# B156X.net
KiCad netlist of a schematic drawn in EAGLE
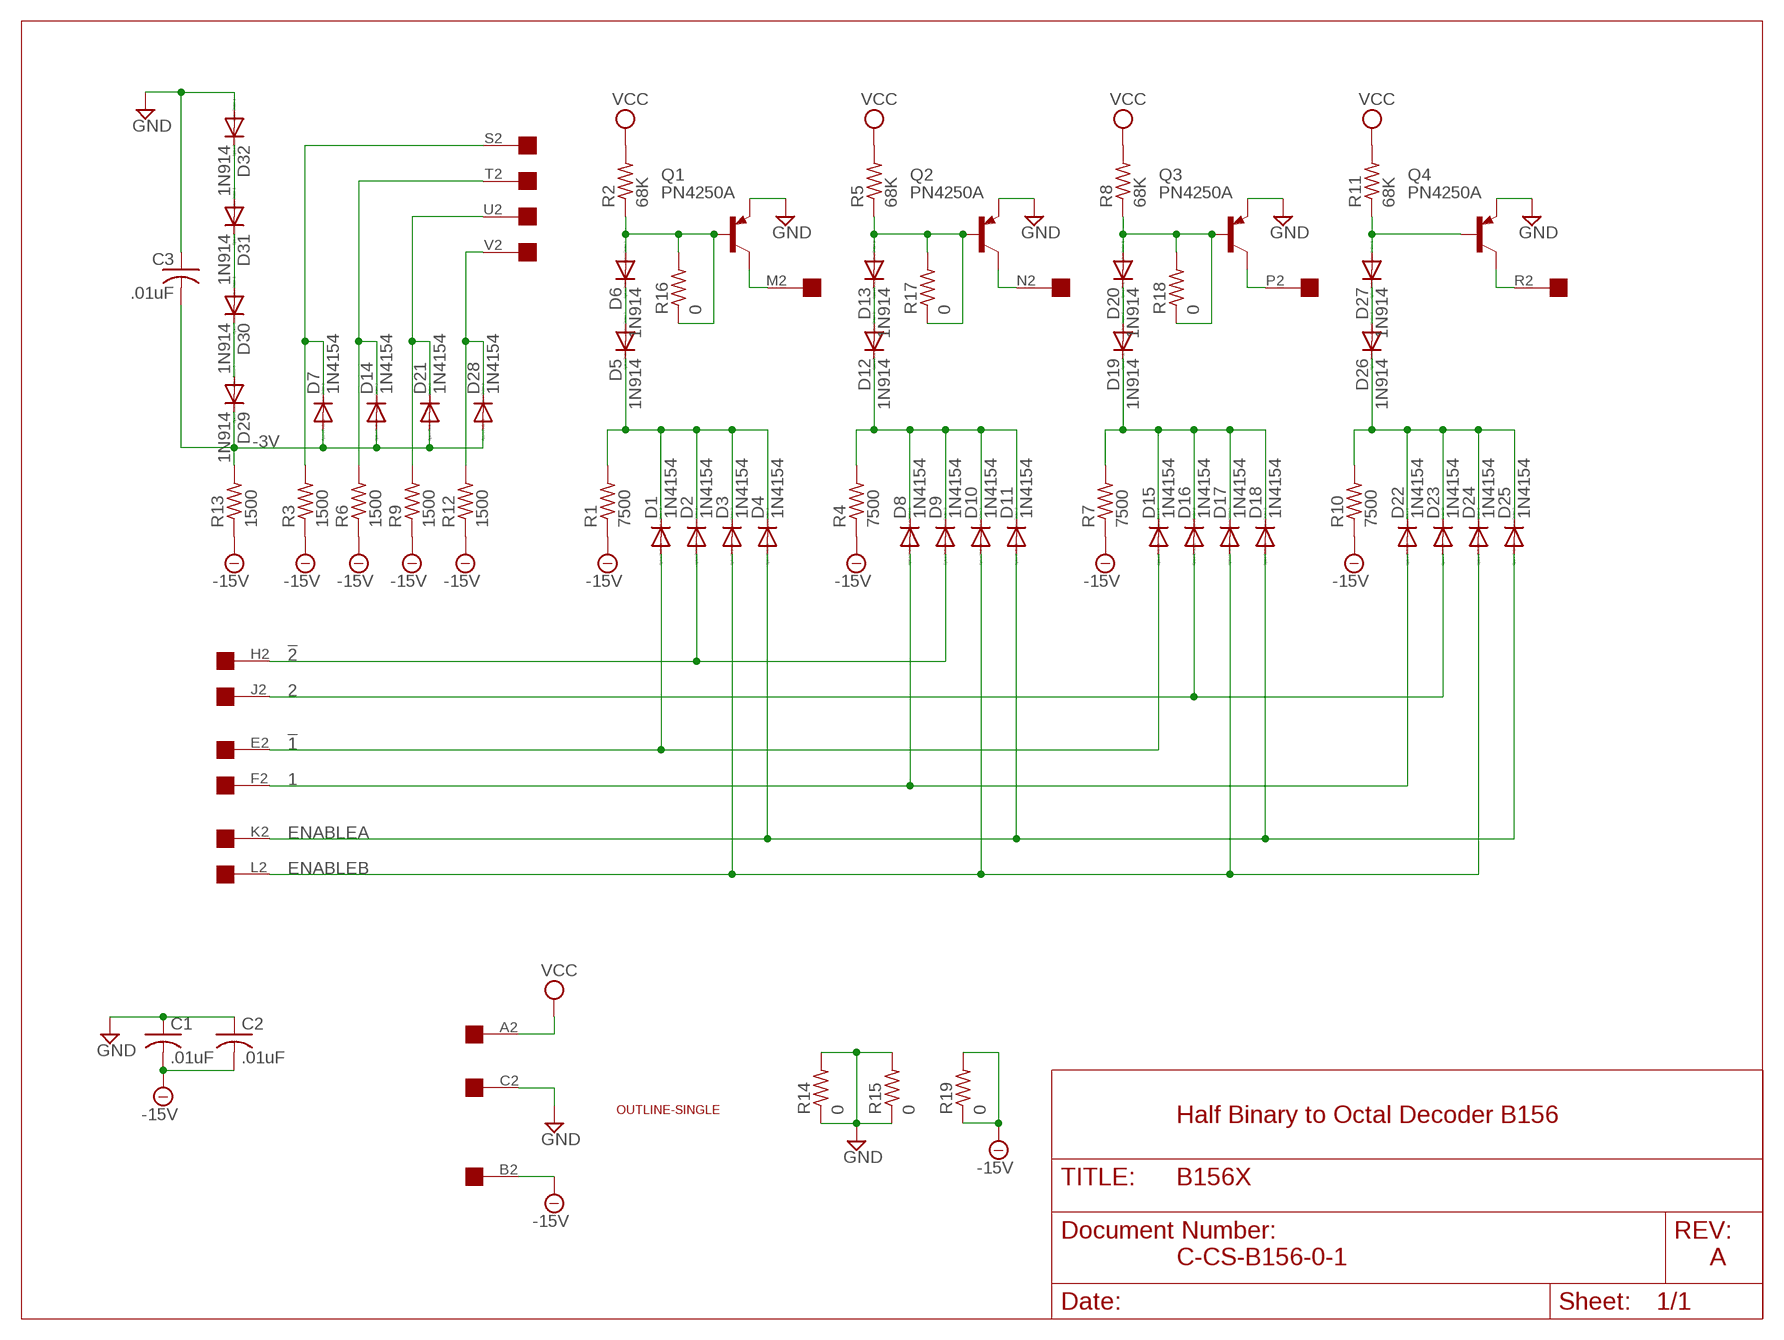
[diagram p0: schematic, sheet 1]

(export (version "E")
  (design (tool "Eeschema 10.0.6"))
  (components
    (comp (ref "C1")
      (value ".01uF")
      (footprint "eagle-import:C063-025X075")
      (libsource (lib "eagle-import") (part "C-US"))
    )
    (comp (ref "C2")
      (value ".01uF")
      (footprint "eagle-import:C063-025X075")
      (libsource (lib "eagle-import") (part "C-US"))
    )
    (comp (ref "C3")
      (value ".01uF")
      (footprint "eagle-import:C063-025X075")
      (libsource (lib "eagle-import") (part "C-US"))
    )
    (comp (ref "D1")
      (value "1N4154")
      (footprint "eagle-import:DO35-10")
      (libsource (lib "eagle-import") (part "DIODE-DO35-10"))
    )
    (comp (ref "D2")
      (value "1N4154")
      (footprint "eagle-import:DO35-10")
      (libsource (lib "eagle-import") (part "DIODE-DO35-10"))
    )
    (comp (ref "D3")
      (value "1N4154")
      (footprint "eagle-import:DO35-10")
      (libsource (lib "eagle-import") (part "DIODE-DO35-10"))
    )
    (comp (ref "D4")
      (value "1N4154")
      (footprint "eagle-import:DO35-10")
      (libsource (lib "eagle-import") (part "DIODE-DO35-10"))
    )
    (comp (ref "D5")
      (value "1N914")
      (footprint "eagle-import:DO35-10")
      (libsource (lib "eagle-import") (part "DIODE-DO35-10"))
    )
    (comp (ref "D6")
      (value "1N914")
      (footprint "eagle-import:DO35-10")
      (libsource (lib "eagle-import") (part "DIODE-DO35-10"))
    )
    (comp (ref "D7")
      (value "1N4154")
      (footprint "eagle-import:DO35-10")
      (libsource (lib "eagle-import") (part "DIODE-DO35-10"))
    )
    (comp (ref "D8")
      (value "1N4154")
      (footprint "eagle-import:DO35-10")
      (libsource (lib "eagle-import") (part "DIODE-DO35-10"))
    )
    (comp (ref "D9")
      (value "1N4154")
      (footprint "eagle-import:DO35-10")
      (libsource (lib "eagle-import") (part "DIODE-DO35-10"))
    )
    (comp (ref "D10")
      (value "1N4154")
      (footprint "eagle-import:DO35-10")
      (libsource (lib "eagle-import") (part "DIODE-DO35-10"))
    )
    (comp (ref "D11")
      (value "1N4154")
      (footprint "eagle-import:DO35-10")
      (libsource (lib "eagle-import") (part "DIODE-DO35-10"))
    )
    (comp (ref "D12")
      (value "1N914")
      (footprint "eagle-import:DO35-10")
      (libsource (lib "eagle-import") (part "DIODE-DO35-10"))
    )
    (comp (ref "D13")
      (value "1N914")
      (footprint "eagle-import:DO35-10")
      (libsource (lib "eagle-import") (part "DIODE-DO35-10"))
    )
    (comp (ref "D14")
      (value "1N4154")
      (footprint "eagle-import:DO35-10")
      (libsource (lib "eagle-import") (part "DIODE-DO35-10"))
    )
    (comp (ref "D15")
      (value "1N4154")
      (footprint "eagle-import:DO35-10")
      (libsource (lib "eagle-import") (part "DIODE-DO35-10"))
    )
    (comp (ref "D16")
      (value "1N4154")
      (footprint "eagle-import:DO35-10")
      (libsource (lib "eagle-import") (part "DIODE-DO35-10"))
    )
    (comp (ref "D17")
      (value "1N4154")
      (footprint "eagle-import:DO35-10")
      (libsource (lib "eagle-import") (part "DIODE-DO35-10"))
    )
    (comp (ref "D18")
      (value "1N4154")
      (footprint "eagle-import:DO35-10")
      (libsource (lib "eagle-import") (part "DIODE-DO35-10"))
    )
    (comp (ref "D19")
      (value "1N914")
      (footprint "eagle-import:DO35-10")
      (libsource (lib "eagle-import") (part "DIODE-DO35-10"))
    )
    (comp (ref "D20")
      (value "1N914")
      (footprint "eagle-import:DO35-10")
      (libsource (lib "eagle-import") (part "DIODE-DO35-10"))
    )
    (comp (ref "D21")
      (value "1N4154")
      (footprint "eagle-import:DO35-10")
      (libsource (lib "eagle-import") (part "DIODE-DO35-10"))
    )
    (comp (ref "D22")
      (value "1N4154")
      (footprint "eagle-import:DO35-10")
      (libsource (lib "eagle-import") (part "DIODE-DO35-10"))
    )
    (comp (ref "D23")
      (value "1N4154")
      (footprint "eagle-import:DO35-10")
      (libsource (lib "eagle-import") (part "DIODE-DO35-10"))
    )
    (comp (ref "D24")
      (value "1N4154")
      (footprint "eagle-import:DO35-10")
      (libsource (lib "eagle-import") (part "DIODE-DO35-10"))
    )
    (comp (ref "D25")
      (value "1N4154")
      (footprint "eagle-import:DO35-10")
      (libsource (lib "eagle-import") (part "DIODE-DO35-10"))
    )
    (comp (ref "D26")
      (value "1N914")
      (footprint "eagle-import:DO35-10")
      (libsource (lib "eagle-import") (part "DIODE-DO35-10"))
    )
    (comp (ref "D27")
      (value "1N914")
      (footprint "eagle-import:DO35-10")
      (libsource (lib "eagle-import") (part "DIODE-DO35-10"))
    )
    (comp (ref "D28")
      (value "1N4154")
      (footprint "eagle-import:DO35-10")
      (libsource (lib "eagle-import") (part "DIODE-DO35-10"))
    )
    (comp (ref "D29")
      (value "1N914")
      (footprint "eagle-import:DO35-10")
      (libsource (lib "eagle-import") (part "DIODE-DO35-10"))
    )
    (comp (ref "D30")
      (value "1N914")
      (footprint "eagle-import:DO35-10")
      (libsource (lib "eagle-import") (part "DIODE-DO35-10"))
    )
    (comp (ref "D31")
      (value "1N914")
      (footprint "eagle-import:DO35-10")
      (libsource (lib "eagle-import") (part "DIODE-DO35-10"))
    )
    (comp (ref "D32")
      (value "1N914")
      (footprint "eagle-import:DO35-10")
      (libsource (lib "eagle-import") (part "DIODE-DO35-10"))
    )
    (comp (ref "Q1")
      (value "PN4250A")
      (footprint "eagle-import:TO5")
      (libsource (lib "eagle-import") (part "-PNP-TO5"))
    )
    (comp (ref "Q2")
      (value "PN4250A")
      (footprint "eagle-import:TO5")
      (libsource (lib "eagle-import") (part "-PNP-TO5"))
    )
    (comp (ref "Q3")
      (value "PN4250A")
      (footprint "eagle-import:TO5")
      (libsource (lib "eagle-import") (part "-PNP-TO5"))
    )
    (comp (ref "Q4")
      (value "PN4250A")
      (footprint "eagle-import:TO5")
      (libsource (lib "eagle-import") (part "-PNP-TO5"))
    )
    (comp (ref "R1")
      (value "7500")
      (footprint "eagle-import:0207_10")
      (libsource (lib "eagle-import") (part "R-US_0207/10"))
    )
    (comp (ref "R2")
      (value "68K")
      (footprint "eagle-import:0207_10")
      (libsource (lib "eagle-import") (part "R-US_0207/10"))
    )
    (comp (ref "R3")
      (value "1500")
      (footprint "eagle-import:0207_10")
      (libsource (lib "eagle-import") (part "R-US_0207/10"))
    )
    (comp (ref "R4")
      (value "7500")
      (footprint "eagle-import:0207_10")
      (libsource (lib "eagle-import") (part "R-US_0207/10"))
    )
    (comp (ref "R5")
      (value "68K")
      (footprint "eagle-import:0207_10")
      (libsource (lib "eagle-import") (part "R-US_0207/10"))
    )
    (comp (ref "R6")
      (value "1500")
      (footprint "eagle-import:0207_10")
      (libsource (lib "eagle-import") (part "R-US_0207/10"))
    )
    (comp (ref "R7")
      (value "7500")
      (footprint "eagle-import:0207_10")
      (libsource (lib "eagle-import") (part "R-US_0207/10"))
    )
    (comp (ref "R8")
      (value "68K")
      (footprint "eagle-import:0207_10")
      (libsource (lib "eagle-import") (part "R-US_0207/10"))
    )
    (comp (ref "R9")
      (value "1500")
      (footprint "eagle-import:0207_10")
      (libsource (lib "eagle-import") (part "R-US_0207/10"))
    )
    (comp (ref "R10")
      (value "7500")
      (footprint "eagle-import:0207_10")
      (libsource (lib "eagle-import") (part "R-US_0207/10"))
    )
    (comp (ref "R11")
      (value "68K")
      (footprint "eagle-import:0207_10")
      (libsource (lib "eagle-import") (part "R-US_0207/10"))
    )
    (comp (ref "R12")
      (value "1500")
      (footprint "eagle-import:0207_10")
      (libsource (lib "eagle-import") (part "R-US_0207/10"))
    )
    (comp (ref "R13")
      (value "1500")
      (footprint "eagle-import:0207_10")
      (libsource (lib "eagle-import") (part "R-US_0207/10"))
    )
    (comp (ref "R14")
      (value "0")
      (footprint "eagle-import:0207_10")
      (libsource (lib "eagle-import") (part "R-US_0207/10"))
    )
    (comp (ref "R15")
      (value "0")
      (footprint "eagle-import:0207_10")
      (libsource (lib "eagle-import") (part "R-US_0207/10"))
    )
    (comp (ref "R16")
      (value "0")
      (footprint "eagle-import:0207_10")
      (libsource (lib "eagle-import") (part "R-US_0207/10"))
    )
    (comp (ref "R17")
      (value "0")
      (footprint "eagle-import:0207_10")
      (libsource (lib "eagle-import") (part "R-US_0207/10"))
    )
    (comp (ref "R18")
      (value "0")
      (footprint "eagle-import:0207_10")
      (libsource (lib "eagle-import") (part "R-US_0207/10"))
    )
    (comp (ref "R19")
      (value "0")
      (footprint "eagle-import:0207_10")
      (libsource (lib "eagle-import") (part "R-US_0207/10"))
    )
    (comp (ref "U$1")
      (value "OUTLINE-SINGLE")
      (footprint "eagle-import:SINGLE")
      (libsource (lib "eagle-import") (part "OUTLINE-SINGLE"))
    )
    (comp (ref "U$2")
      (value "EDGE-1")
      (footprint "eagle-import:EDGE-CON1")
      (libsource (lib "eagle-import") (part "EDGE-1"))
    )
  )
  (nets
    (net (code "1") (name "-15V") (class "Default")
      (node (ref "C1") (pin "2") (pinfunction "2_2") (pintype "passive"))
      (node (ref "C2") (pin "2") (pinfunction "2_2") (pintype "passive"))
      (node (ref "R1") (pin "1") (pinfunction "1_1") (pintype "passive"))
      (node (ref "R10") (pin "1") (pinfunction "1_1") (pintype "passive"))
      (node (ref "R12") (pin "1") (pinfunction "1_1") (pintype "passive"))
      (node (ref "R13") (pin "1") (pinfunction "1_1") (pintype "passive"))
      (node (ref "R19") (pin "1") (pinfunction "1_1") (pintype "passive"))
      (node (ref "R19") (pin "2") (pinfunction "2_2") (pintype "passive"))
      (node (ref "R3") (pin "1") (pinfunction "1_1") (pintype "passive"))
      (node (ref "R4") (pin "1") (pinfunction "1_1") (pintype "passive"))
      (node (ref "R6") (pin "1") (pinfunction "1_1") (pintype "passive"))
      (node (ref "R7") (pin "1") (pinfunction "1_1") (pintype "passive"))
      (node (ref "R9") (pin "1") (pinfunction "1_1") (pintype "passive"))
      (node (ref "U$2") (pin "B2") (pinfunction "1_B2") (pintype "bidirectional"))
    )
    (net (code "2") (name "/-3V") (class "Default")
      (node (ref "C3") (pin "2") (pinfunction "2_2") (pintype "passive"))
      (node (ref "D14") (pin "A") (pinfunction "A_A") (pintype "passive"))
      (node (ref "D21") (pin "A") (pinfunction "A_A") (pintype "passive"))
      (node (ref "D28") (pin "A") (pinfunction "A_A") (pintype "passive"))
      (node (ref "D29") (pin "C") (pinfunction "C_C") (pintype "passive"))
      (node (ref "D7") (pin "A") (pinfunction "A_A") (pintype "passive"))
      (node (ref "R13") (pin "2") (pinfunction "2_2") (pintype "passive"))
    )
    (net (code "3") (name "/1") (class "Default")
      (node (ref "D22") (pin "A") (pinfunction "A_A") (pintype "passive"))
      (node (ref "D8") (pin "A") (pinfunction "A_A") (pintype "passive"))
      (node (ref "U$2") (pin "F2") (pinfunction "1_F2") (pintype "bidirectional"))
    )
    (net (code "4") (name "/2") (class "Default")
      (node (ref "D16") (pin "A") (pinfunction "A_A") (pintype "passive"))
      (node (ref "D23") (pin "A") (pinfunction "A_A") (pintype "passive"))
      (node (ref "U$2") (pin "J2") (pinfunction "1_J2") (pintype "bidirectional"))
    )
    (net (code "5") (name "/ENABLEA") (class "Default")
      (node (ref "D11") (pin "A") (pinfunction "A_A") (pintype "passive"))
      (node (ref "D18") (pin "A") (pinfunction "A_A") (pintype "passive"))
      (node (ref "D25") (pin "A") (pinfunction "A_A") (pintype "passive"))
      (node (ref "D4") (pin "A") (pinfunction "A_A") (pintype "passive"))
      (node (ref "U$2") (pin "K2") (pinfunction "1_K2") (pintype "bidirectional"))
    )
    (net (code "6") (name "/ENABLEB") (class "Default")
      (node (ref "D10") (pin "A") (pinfunction "A_A") (pintype "passive"))
      (node (ref "D17") (pin "A") (pinfunction "A_A") (pintype "passive"))
      (node (ref "D24") (pin "A") (pinfunction "A_A") (pintype "passive"))
      (node (ref "D3") (pin "A") (pinfunction "A_A") (pintype "passive"))
      (node (ref "U$2") (pin "L2") (pinfunction "1_L2") (pintype "bidirectional"))
    )
    (net (code "7") (name "/~{1}") (class "Default")
      (node (ref "D1") (pin "A") (pinfunction "A_A") (pintype "passive"))
      (node (ref "D15") (pin "A") (pinfunction "A_A") (pintype "passive"))
      (node (ref "U$2") (pin "E2") (pinfunction "1_E2") (pintype "bidirectional"))
    )
    (net (code "8") (name "/~{2}") (class "Default")
      (node (ref "D2") (pin "A") (pinfunction "A_A") (pintype "passive"))
      (node (ref "D9") (pin "A") (pinfunction "A_A") (pintype "passive"))
      (node (ref "U$2") (pin "H2") (pinfunction "1_H2") (pintype "bidirectional"))
    )
    (net (code "9") (name "GND") (class "Default")
      (node (ref "C1") (pin "1") (pinfunction "1_1") (pintype "passive"))
      (node (ref "C2") (pin "1") (pinfunction "1_1") (pintype "passive"))
      (node (ref "C3") (pin "1") (pinfunction "1_1") (pintype "passive"))
      (node (ref "D32") (pin "A") (pinfunction "A_A") (pintype "passive"))
      (node (ref "Q1") (pin "1") (pinfunction "E_1") (pintype "passive"))
      (node (ref "Q2") (pin "1") (pinfunction "E_1") (pintype "passive"))
      (node (ref "Q3") (pin "1") (pinfunction "E_1") (pintype "passive"))
      (node (ref "Q4") (pin "1") (pinfunction "E_1") (pintype "passive"))
      (node (ref "R14") (pin "1") (pinfunction "1_1") (pintype "passive"))
      (node (ref "R14") (pin "2") (pinfunction "2_2") (pintype "passive"))
      (node (ref "R15") (pin "1") (pinfunction "1_1") (pintype "passive"))
      (node (ref "R15") (pin "2") (pinfunction "2_2") (pintype "passive"))
      (node (ref "U$2") (pin "C2") (pinfunction "1_C2") (pintype "bidirectional"))
    )
    (net (code "10") (name "Net-(D1-PadC)") (class "Default")
      (node (ref "D1") (pin "C") (pinfunction "C_C") (pintype "passive"))
      (node (ref "D2") (pin "C") (pinfunction "C_C") (pintype "passive"))
      (node (ref "D3") (pin "C") (pinfunction "C_C") (pintype "passive"))
      (node (ref "D4") (pin "C") (pinfunction "C_C") (pintype "passive"))
      (node (ref "D5") (pin "C") (pinfunction "C_C") (pintype "passive"))
      (node (ref "R1") (pin "2") (pinfunction "2_2") (pintype "passive"))
    )
    (net (code "11") (name "Net-(D5-PadA)") (class "Default")
      (node (ref "D5") (pin "A") (pinfunction "A_A") (pintype "passive"))
      (node (ref "D6") (pin "C") (pinfunction "C_C") (pintype "passive"))
    )
    (net (code "12") (name "Net-(D10-PadC)") (class "Default")
      (node (ref "D10") (pin "C") (pinfunction "C_C") (pintype "passive"))
      (node (ref "D11") (pin "C") (pinfunction "C_C") (pintype "passive"))
      (node (ref "D12") (pin "C") (pinfunction "C_C") (pintype "passive"))
      (node (ref "D8") (pin "C") (pinfunction "C_C") (pintype "passive"))
      (node (ref "D9") (pin "C") (pinfunction "C_C") (pintype "passive"))
      (node (ref "R4") (pin "2") (pinfunction "2_2") (pintype "passive"))
    )
    (net (code "13") (name "Net-(D12-PadA)") (class "Default")
      (node (ref "D12") (pin "A") (pinfunction "A_A") (pintype "passive"))
      (node (ref "D13") (pin "C") (pinfunction "C_C") (pintype "passive"))
    )
    (net (code "14") (name "Net-(D15-PadC)") (class "Default")
      (node (ref "D15") (pin "C") (pinfunction "C_C") (pintype "passive"))
      (node (ref "D16") (pin "C") (pinfunction "C_C") (pintype "passive"))
      (node (ref "D17") (pin "C") (pinfunction "C_C") (pintype "passive"))
      (node (ref "D18") (pin "C") (pinfunction "C_C") (pintype "passive"))
      (node (ref "D19") (pin "C") (pinfunction "C_C") (pintype "passive"))
      (node (ref "R7") (pin "2") (pinfunction "2_2") (pintype "passive"))
    )
    (net (code "15") (name "Net-(D19-PadA)") (class "Default")
      (node (ref "D19") (pin "A") (pinfunction "A_A") (pintype "passive"))
      (node (ref "D20") (pin "C") (pinfunction "C_C") (pintype "passive"))
    )
    (net (code "16") (name "Net-(D22-PadC)") (class "Default")
      (node (ref "D22") (pin "C") (pinfunction "C_C") (pintype "passive"))
      (node (ref "D23") (pin "C") (pinfunction "C_C") (pintype "passive"))
      (node (ref "D24") (pin "C") (pinfunction "C_C") (pintype "passive"))
      (node (ref "D25") (pin "C") (pinfunction "C_C") (pintype "passive"))
      (node (ref "D26") (pin "C") (pinfunction "C_C") (pintype "passive"))
      (node (ref "R10") (pin "2") (pinfunction "2_2") (pintype "passive"))
    )
    (net (code "17") (name "Net-(D26-PadA)") (class "Default")
      (node (ref "D26") (pin "A") (pinfunction "A_A") (pintype "passive"))
      (node (ref "D27") (pin "C") (pinfunction "C_C") (pintype "passive"))
    )
    (net (code "18") (name "Net-(D29-PadA)") (class "Default")
      (node (ref "D29") (pin "A") (pinfunction "A_A") (pintype "passive"))
      (node (ref "D30") (pin "C") (pinfunction "C_C") (pintype "passive"))
    )
    (net (code "19") (name "Net-(D30-PadA)") (class "Default")
      (node (ref "D30") (pin "A") (pinfunction "A_A") (pintype "passive"))
      (node (ref "D31") (pin "C") (pinfunction "C_C") (pintype "passive"))
    )
    (net (code "20") (name "Net-(D31-PadA)") (class "Default")
      (node (ref "D31") (pin "A") (pinfunction "A_A") (pintype "passive"))
      (node (ref "D32") (pin "C") (pinfunction "C_C") (pintype "passive"))
    )
    (net (code "21") (name "Net-(Q1-B)") (class "Default")
      (node (ref "D6") (pin "A") (pinfunction "A_A") (pintype "passive"))
      (node (ref "Q1") (pin "2") (pinfunction "B_2") (pintype "passive"))
      (node (ref "R16") (pin "1") (pinfunction "1_1") (pintype "passive"))
      (node (ref "R16") (pin "2") (pinfunction "2_2") (pintype "passive"))
      (node (ref "R2") (pin "1") (pinfunction "1_1") (pintype "passive"))
    )
    (net (code "22") (name "Net-(Q1-C)") (class "Default")
      (node (ref "Q1") (pin "3") (pinfunction "C_3") (pintype "passive"))
      (node (ref "U$2") (pin "M2") (pinfunction "1_M2") (pintype "bidirectional"))
    )
    (net (code "23") (name "Net-(Q2-B)") (class "Default")
      (node (ref "D13") (pin "A") (pinfunction "A_A") (pintype "passive"))
      (node (ref "Q2") (pin "2") (pinfunction "B_2") (pintype "passive"))
      (node (ref "R17") (pin "1") (pinfunction "1_1") (pintype "passive"))
      (node (ref "R17") (pin "2") (pinfunction "2_2") (pintype "passive"))
      (node (ref "R5") (pin "1") (pinfunction "1_1") (pintype "passive"))
    )
    (net (code "24") (name "Net-(Q2-C)") (class "Default")
      (node (ref "Q2") (pin "3") (pinfunction "C_3") (pintype "passive"))
      (node (ref "U$2") (pin "N2") (pinfunction "1_N2") (pintype "bidirectional"))
    )
    (net (code "25") (name "Net-(Q3-B)") (class "Default")
      (node (ref "D20") (pin "A") (pinfunction "A_A") (pintype "passive"))
      (node (ref "Q3") (pin "2") (pinfunction "B_2") (pintype "passive"))
      (node (ref "R18") (pin "1") (pinfunction "1_1") (pintype "passive"))
      (node (ref "R18") (pin "2") (pinfunction "2_2") (pintype "passive"))
      (node (ref "R8") (pin "1") (pinfunction "1_1") (pintype "passive"))
    )
    (net (code "26") (name "Net-(Q3-C)") (class "Default")
      (node (ref "Q3") (pin "3") (pinfunction "C_3") (pintype "passive"))
      (node (ref "U$2") (pin "P2") (pinfunction "1_P2") (pintype "bidirectional"))
    )
    (net (code "27") (name "Net-(Q4-B)") (class "Default")
      (node (ref "D27") (pin "A") (pinfunction "A_A") (pintype "passive"))
      (node (ref "Q4") (pin "2") (pinfunction "B_2") (pintype "passive"))
      (node (ref "R11") (pin "1") (pinfunction "1_1") (pintype "passive"))
    )
    (net (code "28") (name "Net-(Q4-C)") (class "Default")
      (node (ref "Q4") (pin "3") (pinfunction "C_3") (pintype "passive"))
      (node (ref "U$2") (pin "R2") (pinfunction "1_R2") (pintype "bidirectional"))
    )
    (net (code "29") (name "Net-(U$2O-1)") (class "Default")
      (node (ref "D7") (pin "C") (pinfunction "C_C") (pintype "passive"))
      (node (ref "R3") (pin "2") (pinfunction "2_2") (pintype "passive"))
      (node (ref "U$2") (pin "S2") (pinfunction "1_S2") (pintype "bidirectional"))
    )
    (net (code "30") (name "Net-(U$2P-1)") (class "Default")
      (node (ref "D14") (pin "C") (pinfunction "C_C") (pintype "passive"))
      (node (ref "R6") (pin "2") (pinfunction "2_2") (pintype "passive"))
      (node (ref "U$2") (pin "T2") (pinfunction "1_T2") (pintype "bidirectional"))
    )
    (net (code "31") (name "Net-(U$2Q-1)") (class "Default")
      (node (ref "D21") (pin "C") (pinfunction "C_C") (pintype "passive"))
      (node (ref "R9") (pin "2") (pinfunction "2_2") (pintype "passive"))
      (node (ref "U$2") (pin "U2") (pinfunction "1_U2") (pintype "bidirectional"))
    )
    (net (code "32") (name "Net-(U$2R-1)") (class "Default")
      (node (ref "D28") (pin "C") (pinfunction "C_C") (pintype "passive"))
      (node (ref "R12") (pin "2") (pinfunction "2_2") (pintype "passive"))
      (node (ref "U$2") (pin "V2") (pinfunction "1_V2") (pintype "bidirectional"))
    )
    (net (code "33") (name "VCC") (class "Default")
      (node (ref "R11") (pin "2") (pinfunction "2_2") (pintype "passive"))
      (node (ref "R2") (pin "2") (pinfunction "2_2") (pintype "passive"))
      (node (ref "R5") (pin "2") (pinfunction "2_2") (pintype "passive"))
      (node (ref "R8") (pin "2") (pinfunction "2_2") (pintype "passive"))
      (node (ref "U$2") (pin "A2") (pinfunction "1_A2") (pintype "bidirectional"))
    )
  )
)
